# receiver_am26c32.net
KiCad netlist of a schematic drawn in Altium Designer
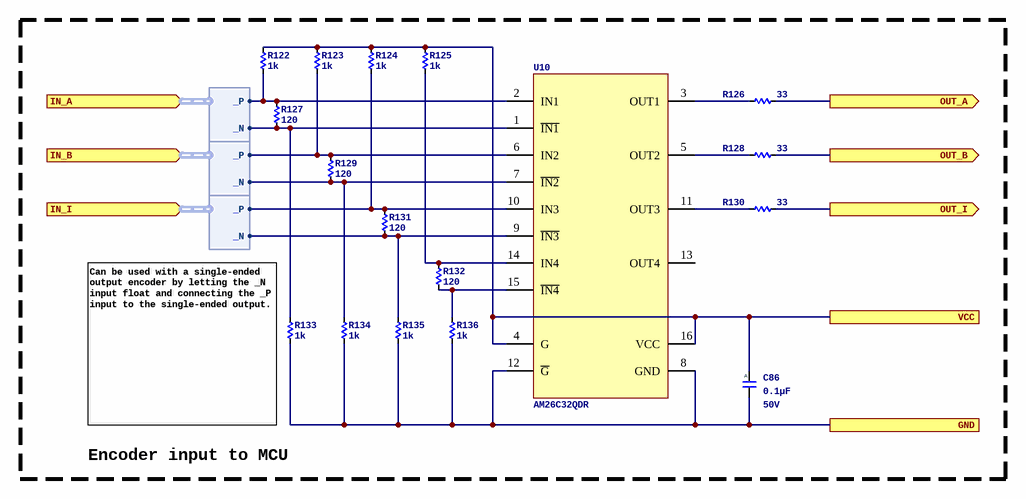
[diagram p0: receiver_am26c32.SchDoc]

(export (version "E")
  (design (tool "Eeschema 10.0.6"))
  (components
    (comp (ref "C86")
      (value "CGA2B3X7R1H104M050BB")
      (footprint "C0402_0.55MM")
      (description "CAP CER 0.1UF 50V X7R 0402")
      (fields
        (field (name "CAPACITANCE") "0.1µF")
        (field (name "VOLTAGE - RATED") "50V")
        (field (name "TOLERANCE") "±20%")
        (field (name "MANUFACTURER") "TDK Corporation")
      )
      (libsource (lib "sscp") (part "__template_cap_auto"))
    )
    (comp (ref "R122")
      (value "~")
      (footprint "R0402_0.40MM")
      (description "RES SMD 1K OHM 1% 1/10W 0402")
      (fields (field (name "RESISTANCE") "1k") (field (name "TOLERANCE") "±1%"))
      (libsource (lib "sscp") (part "__template_resistor"))
    )
    (comp (ref "R123")
      (value "~")
      (footprint "R0402_0.40MM")
      (description "RES SMD 1K OHM 1% 1/10W 0402")
      (fields (field (name "RESISTANCE") "1k") (field (name "TOLERANCE") "±1%"))
      (libsource (lib "sscp") (part "__template_resistor"))
    )
    (comp (ref "R124")
      (value "~")
      (footprint "R0402_0.40MM")
      (description "RES SMD 1K OHM 1% 1/10W 0402")
      (fields (field (name "RESISTANCE") "1k") (field (name "TOLERANCE") "±1%"))
      (libsource (lib "sscp") (part "__template_resistor"))
    )
    (comp (ref "R125")
      (value "~")
      (footprint "R0402_0.40MM")
      (description "RES SMD 1K OHM 1% 1/10W 0402")
      (fields (field (name "RESISTANCE") "1k") (field (name "TOLERANCE") "±1%"))
      (libsource (lib "sscp") (part "__template_resistor"))
    )
    (comp (ref "R126")
      (value "ERJ-2RKF33R0X")
      (footprint "R0402_0.40MM")
      (description "RES SMD 33 OHM 1% 1/10W 0402")
      (fields
        (field (name "RESISTANCE") "33")
        (field (name "TOLERANCE") "±1%")
        (field (name "MANUFACTURER") "Panasonic Electronic Components")
      )
      (libsource (lib "sscp") (part "__template_resistor"))
    )
    (comp (ref "R127")
      (value "ERJ-6ENF1200V")
      (footprint "R0805_0.70MM")
      (description "RES SMD 120 OHM 1% 1/8W 0805")
      (fields
        (field (name "RESISTANCE") "120")
        (field (name "TOLERANCE") "±1%")
        (field (name "MANUFACTURER") "Panasonic Electronic Components")
      )
      (libsource (lib "sscp") (part "__template_resistor"))
    )
    (comp (ref "R128")
      (value "ERJ-2RKF33R0X")
      (footprint "R0402_0.40MM")
      (description "RES SMD 33 OHM 1% 1/10W 0402")
      (fields
        (field (name "RESISTANCE") "33")
        (field (name "TOLERANCE") "±1%")
        (field (name "MANUFACTURER") "Panasonic Electronic Components")
      )
      (libsource (lib "sscp") (part "__template_resistor"))
    )
    (comp (ref "R129")
      (value "ERJ-6ENF1200V")
      (footprint "R0805_0.70MM")
      (description "RES SMD 120 OHM 1% 1/8W 0805")
      (fields
        (field (name "RESISTANCE") "120")
        (field (name "TOLERANCE") "±1%")
        (field (name "MANUFACTURER") "Panasonic Electronic Components")
      )
      (libsource (lib "sscp") (part "__template_resistor"))
    )
    (comp (ref "R130")
      (value "ERJ-2RKF33R0X")
      (footprint "R0402_0.40MM")
      (description "RES SMD 33 OHM 1% 1/10W 0402")
      (fields
        (field (name "RESISTANCE") "33")
        (field (name "TOLERANCE") "±1%")
        (field (name "MANUFACTURER") "Panasonic Electronic Components")
      )
      (libsource (lib "sscp") (part "__template_resistor"))
    )
    (comp (ref "R131")
      (value "ERJ-6ENF1200V")
      (footprint "R0805_0.70MM")
      (description "RES SMD 120 OHM 1% 1/8W 0805")
      (fields
        (field (name "RESISTANCE") "120")
        (field (name "TOLERANCE") "±1%")
        (field (name "MANUFACTURER") "Panasonic Electronic Components")
      )
      (libsource (lib "sscp") (part "__template_resistor"))
    )
    (comp (ref "R132")
      (value "ERJ-6ENF1200V")
      (footprint "R0805_0.70MM")
      (description "RES SMD 120 OHM 1% 1/8W 0805")
      (fields
        (field (name "RESISTANCE") "120")
        (field (name "TOLERANCE") "±1%")
        (field (name "MANUFACTURER") "Panasonic Electronic Components")
      )
      (libsource (lib "sscp") (part "__template_resistor"))
    )
    (comp (ref "R133")
      (value "~")
      (footprint "R0402_0.40MM")
      (description "RES SMD 1K OHM 1% 1/10W 0402")
      (fields (field (name "RESISTANCE") "1k") (field (name "TOLERANCE") "±1%"))
      (libsource (lib "sscp") (part "__template_resistor"))
    )
    (comp (ref "R134")
      (value "~")
      (footprint "R0402_0.40MM")
      (description "RES SMD 1K OHM 1% 1/10W 0402")
      (fields (field (name "RESISTANCE") "1k") (field (name "TOLERANCE") "±1%"))
      (libsource (lib "sscp") (part "__template_resistor"))
    )
    (comp (ref "R135")
      (value "~")
      (footprint "R0402_0.40MM")
      (description "RES SMD 1K OHM 1% 1/10W 0402")
      (fields (field (name "RESISTANCE") "1k") (field (name "TOLERANCE") "±1%"))
      (libsource (lib "sscp") (part "__template_resistor"))
    )
    (comp (ref "R136")
      (value "~")
      (footprint "R0402_0.40MM")
      (description "RES SMD 1K OHM 1% 1/10W 0402")
      (fields (field (name "RESISTANCE") "1k") (field (name "TOLERANCE") "±1%"))
      (libsource (lib "sscp") (part "__template_resistor"))
    )
    (comp (ref "U10")
      (value "AM26C32QDR")
      (footprint "16SOIC150")
      (description "Quadruple Differential Line Receiver 16-SOIC -40 to 125")
      (fields (field (name "MANUFACTURER") "Texas Instruments"))
      (libsource (lib "SSCP") (part "RS422_AM26C32QDR"))
    )
  )
  (nets
    (net (code "3") (name "/GND") (class "Default")
      (node (ref "C86") (pin "2") (pintype "passive"))
      (node (ref "R133") (pin "2") (pintype "passive"))
      (node (ref "R134") (pin "2") (pintype "passive"))
      (node (ref "R135") (pin "2") (pintype "passive"))
      (node (ref "R136") (pin "2") (pintype "passive"))
      (node (ref "U10") (pin "12") (pinfunction "~{G}_12") (pintype "passive"))
      (node (ref "U10") (pin "8") (pinfunction "GND_8") (pintype "passive"))
    )
    (net (code "5") (name "/OUT_A") (class "Default") (node (ref "R126") (pin "1") (pintype "passive")))
    (net (code "6") (name "/OUT_B") (class "Default") (node (ref "R128") (pin "1") (pintype "passive")))
    (net (code "7") (name "/OUT_I") (class "Default") (node (ref "R130") (pin "1") (pintype "passive")))
    (net (code "8") (name "/VCC") (class "Default")
      (node (ref "C86") (pin "1") (pintype "passive"))
      (node (ref "R122") (pin "1") (pintype "passive"))
      (node (ref "R123") (pin "1") (pintype "passive"))
      (node (ref "R124") (pin "1") (pintype "passive"))
      (node (ref "R125") (pin "1") (pintype "passive"))
      (node (ref "U10") (pin "16") (pinfunction "VCC_16") (pintype "passive"))
      (node (ref "U10") (pin "4") (pinfunction "G_4") (pintype "passive"))
    )
    (net (code "10") (name "Net-(U10-IN1)") (class "Default")
      (node (ref "R122") (pin "2") (pintype "passive"))
      (node (ref "R127") (pin "1") (pintype "passive"))
      (node (ref "U10") (pin "2") (pinfunction "IN1_2") (pintype "passive"))
    )
    (net (code "11") (name "Net-(U10-IN2)") (class "Default")
      (node (ref "R123") (pin "2") (pintype "passive"))
      (node (ref "R129") (pin "1") (pintype "passive"))
      (node (ref "U10") (pin "6") (pinfunction "IN2_6") (pintype "passive"))
    )
    (net (code "12") (name "Net-(U10-IN3)") (class "Default")
      (node (ref "R124") (pin "2") (pintype "passive"))
      (node (ref "R131") (pin "1") (pintype "passive"))
      (node (ref "U10") (pin "10") (pinfunction "IN3_10") (pintype "passive"))
    )
    (net (code "13") (name "Net-(U10-IN4)") (class "Default")
      (node (ref "R125") (pin "2") (pintype "passive"))
      (node (ref "R132") (pin "1") (pintype "passive"))
      (node (ref "U10") (pin "14") (pinfunction "IN4_14") (pintype "passive"))
    )
    (net (code "14") (name "Net-(U10-OUT1)") (class "Default")
      (node (ref "R126") (pin "2") (pintype "passive"))
      (node (ref "U10") (pin "3") (pinfunction "OUT1_3") (pintype "passive"))
    )
    (net (code "15") (name "Net-(U10-OUT2)") (class "Default")
      (node (ref "R128") (pin "2") (pintype "passive"))
      (node (ref "U10") (pin "5") (pinfunction "OUT2_5") (pintype "passive"))
    )
    (net (code "16") (name "Net-(U10-OUT3)") (class "Default")
      (node (ref "R130") (pin "2") (pintype "passive"))
      (node (ref "U10") (pin "11") (pinfunction "OUT3_11") (pintype "passive"))
    )
    (net (code "17") (name "Net-(U10-~{IN1})") (class "Default")
      (node (ref "R127") (pin "2") (pintype "passive"))
      (node (ref "R133") (pin "1") (pintype "passive"))
      (node (ref "U10") (pin "1") (pinfunction "~{IN1}_1") (pintype "passive"))
    )
    (net (code "18") (name "Net-(U10-~{IN2})") (class "Default")
      (node (ref "R129") (pin "2") (pintype "passive"))
      (node (ref "R134") (pin "1") (pintype "passive"))
      (node (ref "U10") (pin "7") (pinfunction "~{IN2}_7") (pintype "passive"))
    )
    (net (code "19") (name "Net-(U10-~{IN3})") (class "Default")
      (node (ref "R131") (pin "2") (pintype "passive"))
      (node (ref "R135") (pin "1") (pintype "passive"))
      (node (ref "U10") (pin "9") (pinfunction "~{IN3}_9") (pintype "passive"))
    )
    (net (code "20") (name "Net-(U10-~{IN4})") (class "Default")
      (node (ref "R132") (pin "2") (pintype "passive"))
      (node (ref "R136") (pin "1") (pintype "passive"))
      (node (ref "U10") (pin "15") (pinfunction "~{IN4}_15") (pintype "passive"))
    )
    (net (code "21") (name "unconnected-(U10-OUT4-Pad13)") (class "Default")
      (node (ref "U10") (pin "13") (pinfunction "OUT4_13") (pintype "passive"))
    )
  )
)
